# InnerRing.net
KiCad netlist of a schematic drawn in Altium Designer
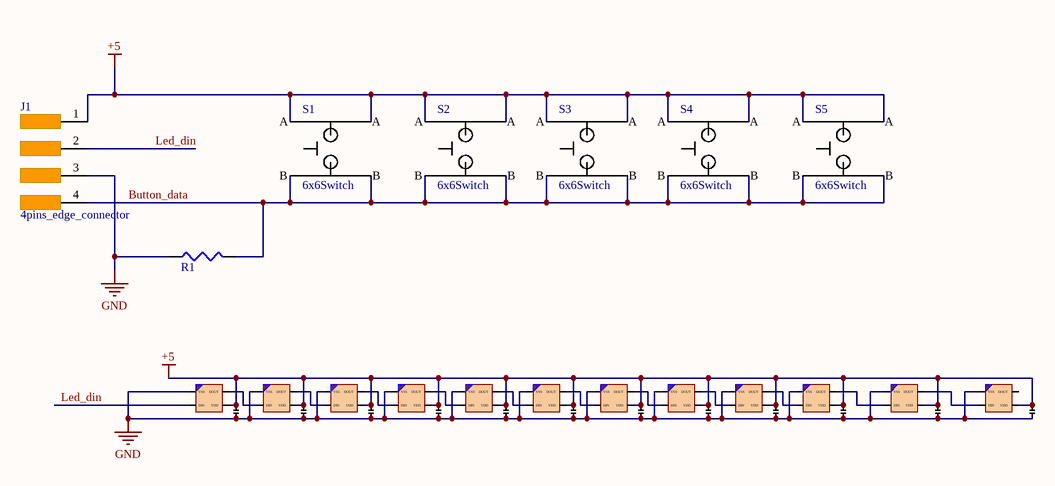
[diagram p0: InnerRing.SchDoc]

(export (version "E")
  (design (tool "Eeschema 10.0.6"))
  (components
    (comp (ref "C1")
      (value "capacitor0.1uf")
      (footprint "Capacitor0805")
      (description "for leds and smol")
      (libsource (lib "WTFschlibra") (part "capacitor0.1uf"))
    )
    (comp (ref "C2")
      (value "capacitor0.1uf")
      (footprint "Capacitor0805")
      (description "for leds and smol")
      (libsource (lib "WTFschlibra") (part "capacitor0.1uf"))
    )
    (comp (ref "C3")
      (value "capacitor0.1uf")
      (footprint "Capacitor0805")
      (description "for leds and smol")
      (libsource (lib "WTFschlibra") (part "capacitor0.1uf"))
    )
    (comp (ref "C4")
      (value "capacitor0.1uf")
      (footprint "Capacitor0805")
      (description "for leds and smol")
      (libsource (lib "WTFschlibra") (part "capacitor0.1uf"))
    )
    (comp (ref "C5")
      (value "capacitor0.1uf")
      (footprint "Capacitor0805")
      (description "for leds and smol")
      (libsource (lib "WTFschlibra") (part "capacitor0.1uf"))
    )
    (comp (ref "C6")
      (value "capacitor0.1uf")
      (footprint "Capacitor0805")
      (description "for leds and smol")
      (libsource (lib "WTFschlibra") (part "capacitor0.1uf"))
    )
    (comp (ref "C7")
      (value "capacitor0.1uf")
      (footprint "Capacitor0805")
      (description "for leds and smol")
      (libsource (lib "WTFschlibra") (part "capacitor0.1uf"))
    )
    (comp (ref "C8")
      (value "capacitor0.1uf")
      (footprint "Capacitor0805")
      (description "for leds and smol")
      (libsource (lib "WTFschlibra") (part "capacitor0.1uf"))
    )
    (comp (ref "C9")
      (value "capacitor0.1uf")
      (footprint "Capacitor0805")
      (description "for leds and smol")
      (libsource (lib "WTFschlibra") (part "capacitor0.1uf"))
    )
    (comp (ref "C10")
      (value "capacitor0.1uf")
      (footprint "Capacitor0805")
      (description "for leds and smol")
      (libsource (lib "WTFschlibra") (part "capacitor0.1uf"))
    )
    (comp (ref "C11")
      (value "capacitor0.1uf")
      (footprint "Capacitor0805")
      (description "for leds and smol")
      (libsource (lib "WTFschlibra") (part "capacitor0.1uf"))
    )
    (comp (ref "C12")
      (value "capacitor0.1uf")
      (footprint "Capacitor0805")
      (description "for leds and smol")
      (libsource (lib "WTFschlibra") (part "capacitor0.1uf"))
    )
    (comp (ref "J1")
      (value "4pins_edge_connector")
      (footprint "4pins_edge_connector")
      (libsource (lib "WTFschlibra") (part "4pins_edge_connector"))
    )
    (comp (ref "LED1")
      (value "Ws2812B")
      (footprint "ws2812b")
      (libsource (lib "WTFschlibra") (part "Ws2812B"))
    )
    (comp (ref "LED2")
      (value "Ws2812B")
      (footprint "ws2812b")
      (libsource (lib "WTFschlibra") (part "Ws2812B"))
    )
    (comp (ref "LED3")
      (value "Ws2812B")
      (footprint "ws2812b")
      (libsource (lib "WTFschlibra") (part "Ws2812B"))
    )
    (comp (ref "LED4")
      (value "Ws2812B")
      (footprint "ws2812b")
      (libsource (lib "WTFschlibra") (part "Ws2812B"))
    )
    (comp (ref "LED5")
      (value "Ws2812B")
      (footprint "ws2812b")
      (libsource (lib "WTFschlibra") (part "Ws2812B"))
    )
    (comp (ref "LED6")
      (value "Ws2812B")
      (footprint "ws2812b")
      (libsource (lib "WTFschlibra") (part "Ws2812B"))
    )
    (comp (ref "LED7")
      (value "Ws2812B")
      (footprint "ws2812b")
      (libsource (lib "WTFschlibra") (part "Ws2812B"))
    )
    (comp (ref "LED8")
      (value "Ws2812B")
      (footprint "ws2812b")
      (libsource (lib "WTFschlibra") (part "Ws2812B"))
    )
    (comp (ref "LED9")
      (value "Ws2812B")
      (footprint "ws2812b")
      (libsource (lib "WTFschlibra") (part "Ws2812B"))
    )
    (comp (ref "LED10")
      (value "Ws2812B")
      (footprint "ws2812b")
      (libsource (lib "WTFschlibra") (part "Ws2812B"))
    )
    (comp (ref "LED11")
      (value "Ws2812B")
      (footprint "ws2812b")
      (libsource (lib "WTFschlibra") (part "Ws2812B"))
    )
    (comp (ref "LED12")
      (value "Ws2812B")
      (footprint "ws2812b")
      (libsource (lib "WTFschlibra") (part "Ws2812B"))
    )
    (comp (ref "R1")
      (value "10K")
      (footprint "R0805")
      (description "Res Thick Film 0805 360 Ohm 1% 0.125W(1/8W) ±100ppm/C Molded SMD Automotive Paper T/R")
      (fields (field (name "TOLERANCE") "1%"))
      (libsource (lib "WTFschlibra") (part "resistor(CRCW0805360RFKEA"))
    )
    (comp (ref "S1")
      (value "6x6Switch")
      (footprint "6x6Switch")
      (libsource (lib "WTFschlibra") (part "6x6Switch"))
    )
    (comp (ref "S2")
      (value "6x6Switch")
      (footprint "6x6Switch")
      (libsource (lib "WTFschlibra") (part "6x6Switch"))
    )
    (comp (ref "S3")
      (value "6x6Switch")
      (footprint "6x6Switch")
      (libsource (lib "WTFschlibra") (part "6x6Switch"))
    )
    (comp (ref "S4")
      (value "6x6Switch")
      (footprint "6x6Switch")
      (libsource (lib "WTFschlibra") (part "6x6Switch"))
    )
    (comp (ref "S5")
      (value "6x6Switch")
      (footprint "6x6Switch")
      (libsource (lib "WTFschlibra") (part "6x6Switch"))
    )
  )
  (nets
    (net (code "1") (name "+5") (class "Default")
      (node (ref "C1") (pin "2") (pinfunction "+_2") (pintype "passive"))
      (node (ref "C10") (pin "2") (pinfunction "+_2") (pintype "passive"))
      (node (ref "C11") (pin "2") (pinfunction "+_2") (pintype "passive"))
      (node (ref "C12") (pin "2") (pinfunction "+_2") (pintype "passive"))
      (node (ref "C2") (pin "2") (pinfunction "+_2") (pintype "passive"))
      (node (ref "C3") (pin "2") (pinfunction "+_2") (pintype "passive"))
      (node (ref "C4") (pin "2") (pinfunction "+_2") (pintype "passive"))
      (node (ref "C5") (pin "2") (pinfunction "+_2") (pintype "passive"))
      (node (ref "C6") (pin "2") (pinfunction "+_2") (pintype "passive"))
      (node (ref "C7") (pin "2") (pinfunction "+_2") (pintype "passive"))
      (node (ref "C8") (pin "2") (pinfunction "+_2") (pintype "passive"))
      (node (ref "C9") (pin "2") (pinfunction "+_2") (pintype "passive"))
      (node (ref "J1") (pin "1") (pinfunction "+5v_1") (pintype "passive"))
      (node (ref "LED1") (pin "1") (pinfunction "VDD_1") (pintype "passive"))
      (node (ref "LED10") (pin "1") (pinfunction "VDD_1") (pintype "passive"))
      (node (ref "LED11") (pin "1") (pinfunction "VDD_1") (pintype "passive"))
      (node (ref "LED12") (pin "1") (pinfunction "VDD_1") (pintype "passive"))
      (node (ref "LED2") (pin "1") (pinfunction "VDD_1") (pintype "passive"))
      (node (ref "LED3") (pin "1") (pinfunction "VDD_1") (pintype "passive"))
      (node (ref "LED4") (pin "1") (pinfunction "VDD_1") (pintype "passive"))
      (node (ref "LED5") (pin "1") (pinfunction "VDD_1") (pintype "passive"))
      (node (ref "LED6") (pin "1") (pinfunction "VDD_1") (pintype "passive"))
      (node (ref "LED7") (pin "1") (pinfunction "VDD_1") (pintype "passive"))
      (node (ref "LED8") (pin "1") (pinfunction "VDD_1") (pintype "passive"))
      (node (ref "LED9") (pin "1") (pinfunction "VDD_1") (pintype "passive"))
      (node (ref "S1") (pin "1") (pinfunction "A_1") (pintype "passive"))
      (node (ref "S1") (pin "4") (pinfunction "A_4") (pintype "passive"))
      (node (ref "S2") (pin "1") (pinfunction "A_1") (pintype "passive"))
      (node (ref "S2") (pin "4") (pinfunction "A_4") (pintype "passive"))
      (node (ref "S3") (pin "1") (pinfunction "A_1") (pintype "passive"))
      (node (ref "S3") (pin "4") (pinfunction "A_4") (pintype "passive"))
      (node (ref "S4") (pin "1") (pinfunction "A_1") (pintype "passive"))
      (node (ref "S4") (pin "4") (pinfunction "A_4") (pintype "passive"))
      (node (ref "S5") (pin "1") (pinfunction "A_1") (pintype "passive"))
      (node (ref "S5") (pin "4") (pinfunction "A_4") (pintype "passive"))
    )
    (net (code "2") (name "/Button_data") (class "Default")
      (node (ref "J1") (pin "4") (pinfunction "Button_4") (pintype "passive"))
      (node (ref "R1") (pin "2") (pinfunction "2_2") (pintype "passive"))
      (node (ref "S1") (pin "2") (pinfunction "B_2") (pintype "passive"))
      (node (ref "S1") (pin "3") (pinfunction "B_3") (pintype "passive"))
      (node (ref "S2") (pin "2") (pinfunction "B_2") (pintype "passive"))
      (node (ref "S2") (pin "3") (pinfunction "B_3") (pintype "passive"))
      (node (ref "S3") (pin "2") (pinfunction "B_2") (pintype "passive"))
      (node (ref "S3") (pin "3") (pinfunction "B_3") (pintype "passive"))
      (node (ref "S4") (pin "2") (pinfunction "B_2") (pintype "passive"))
      (node (ref "S4") (pin "3") (pinfunction "B_3") (pintype "passive"))
      (node (ref "S5") (pin "2") (pinfunction "B_2") (pintype "passive"))
      (node (ref "S5") (pin "3") (pinfunction "B_3") (pintype "passive"))
    )
    (net (code "3") (name "/Led_din") (class "Default")
      (node (ref "J1") (pin "2") (pinfunction "Data_2") (pintype "passive"))
      (node (ref "LED1") (pin "4") (pinfunction "DIN_4") (pintype "passive"))
    )
    (net (code "4") (name "GND") (class "Default")
      (node (ref "C1") (pin "1") (pinfunction "-_1") (pintype "passive"))
      (node (ref "C10") (pin "1") (pinfunction "-_1") (pintype "passive"))
      (node (ref "C11") (pin "1") (pinfunction "-_1") (pintype "passive"))
      (node (ref "C12") (pin "1") (pinfunction "-_1") (pintype "passive"))
      (node (ref "C2") (pin "1") (pinfunction "-_1") (pintype "passive"))
      (node (ref "C3") (pin "1") (pinfunction "-_1") (pintype "passive"))
      (node (ref "C4") (pin "1") (pinfunction "-_1") (pintype "passive"))
      (node (ref "C5") (pin "1") (pinfunction "-_1") (pintype "passive"))
      (node (ref "C6") (pin "1") (pinfunction "-_1") (pintype "passive"))
      (node (ref "C7") (pin "1") (pinfunction "-_1") (pintype "passive"))
      (node (ref "C8") (pin "1") (pinfunction "-_1") (pintype "passive"))
      (node (ref "C9") (pin "1") (pinfunction "-_1") (pintype "passive"))
      (node (ref "J1") (pin "3") (pinfunction "GND_3") (pintype "passive"))
      (node (ref "LED1") (pin "3") (pinfunction "VSS_3") (pintype "passive"))
      (node (ref "LED10") (pin "3") (pinfunction "VSS_3") (pintype "passive"))
      (node (ref "LED11") (pin "3") (pinfunction "VSS_3") (pintype "passive"))
      (node (ref "LED12") (pin "3") (pinfunction "VSS_3") (pintype "passive"))
      (node (ref "LED2") (pin "3") (pinfunction "VSS_3") (pintype "passive"))
      (node (ref "LED3") (pin "3") (pinfunction "VSS_3") (pintype "passive"))
      (node (ref "LED4") (pin "3") (pinfunction "VSS_3") (pintype "passive"))
      (node (ref "LED5") (pin "3") (pinfunction "VSS_3") (pintype "passive"))
      (node (ref "LED6") (pin "3") (pinfunction "VSS_3") (pintype "passive"))
      (node (ref "LED7") (pin "3") (pinfunction "VSS_3") (pintype "passive"))
      (node (ref "LED8") (pin "3") (pinfunction "VSS_3") (pintype "passive"))
      (node (ref "LED9") (pin "3") (pinfunction "VSS_3") (pintype "passive"))
      (node (ref "R1") (pin "1") (pinfunction "1_1") (pintype "passive"))
    )
    (net (code "5") (name "Net-(LED1-DOUT)") (class "Default")
      (node (ref "LED1") (pin "2") (pinfunction "DOUT_2") (pintype "passive"))
      (node (ref "LED2") (pin "4") (pinfunction "DIN_4") (pintype "passive"))
    )
    (net (code "6") (name "Net-(LED2-DOUT)") (class "Default")
      (node (ref "LED2") (pin "2") (pinfunction "DOUT_2") (pintype "passive"))
      (node (ref "LED3") (pin "4") (pinfunction "DIN_4") (pintype "passive"))
    )
    (net (code "7") (name "Net-(LED3-DOUT)") (class "Default")
      (node (ref "LED3") (pin "2") (pinfunction "DOUT_2") (pintype "passive"))
      (node (ref "LED4") (pin "4") (pinfunction "DIN_4") (pintype "passive"))
    )
    (net (code "8") (name "Net-(LED4-DOUT)") (class "Default")
      (node (ref "LED4") (pin "2") (pinfunction "DOUT_2") (pintype "passive"))
      (node (ref "LED5") (pin "4") (pinfunction "DIN_4") (pintype "passive"))
    )
    (net (code "9") (name "Net-(LED5-DOUT)") (class "Default")
      (node (ref "LED5") (pin "2") (pinfunction "DOUT_2") (pintype "passive"))
      (node (ref "LED6") (pin "4") (pinfunction "DIN_4") (pintype "passive"))
    )
    (net (code "10") (name "Net-(LED6-DOUT)") (class "Default")
      (node (ref "LED6") (pin "2") (pinfunction "DOUT_2") (pintype "passive"))
      (node (ref "LED7") (pin "4") (pinfunction "DIN_4") (pintype "passive"))
    )
    (net (code "11") (name "Net-(LED7-DOUT)") (class "Default")
      (node (ref "LED7") (pin "2") (pinfunction "DOUT_2") (pintype "passive"))
      (node (ref "LED8") (pin "4") (pinfunction "DIN_4") (pintype "passive"))
    )
    (net (code "12") (name "Net-(LED8-DOUT)") (class "Default")
      (node (ref "LED8") (pin "2") (pinfunction "DOUT_2") (pintype "passive"))
      (node (ref "LED9") (pin "4") (pinfunction "DIN_4") (pintype "passive"))
    )
    (net (code "13") (name "Net-(LED10-DIN)") (class "Default")
      (node (ref "LED10") (pin "4") (pinfunction "DIN_4") (pintype "passive"))
      (node (ref "LED9") (pin "2") (pinfunction "DOUT_2") (pintype "passive"))
    )
    (net (code "14") (name "Net-(LED10-DOUT)") (class "Default")
      (node (ref "LED10") (pin "2") (pinfunction "DOUT_2") (pintype "passive"))
      (node (ref "LED11") (pin "4") (pinfunction "DIN_4") (pintype "passive"))
    )
    (net (code "15") (name "Net-(LED11-DOUT)") (class "Default")
      (node (ref "LED11") (pin "2") (pinfunction "DOUT_2") (pintype "passive"))
      (node (ref "LED12") (pin "4") (pinfunction "DIN_4") (pintype "passive"))
    )
    (net (code "16") (name "unconnected-(LED12-DOUT-Pad2)") (class "Default")
      (node (ref "LED12") (pin "2") (pinfunction "DOUT_2") (pintype "passive"))
    )
  )
)
